# psx-mc.net
KiCad netlist of a schematic drawn in EAGLE
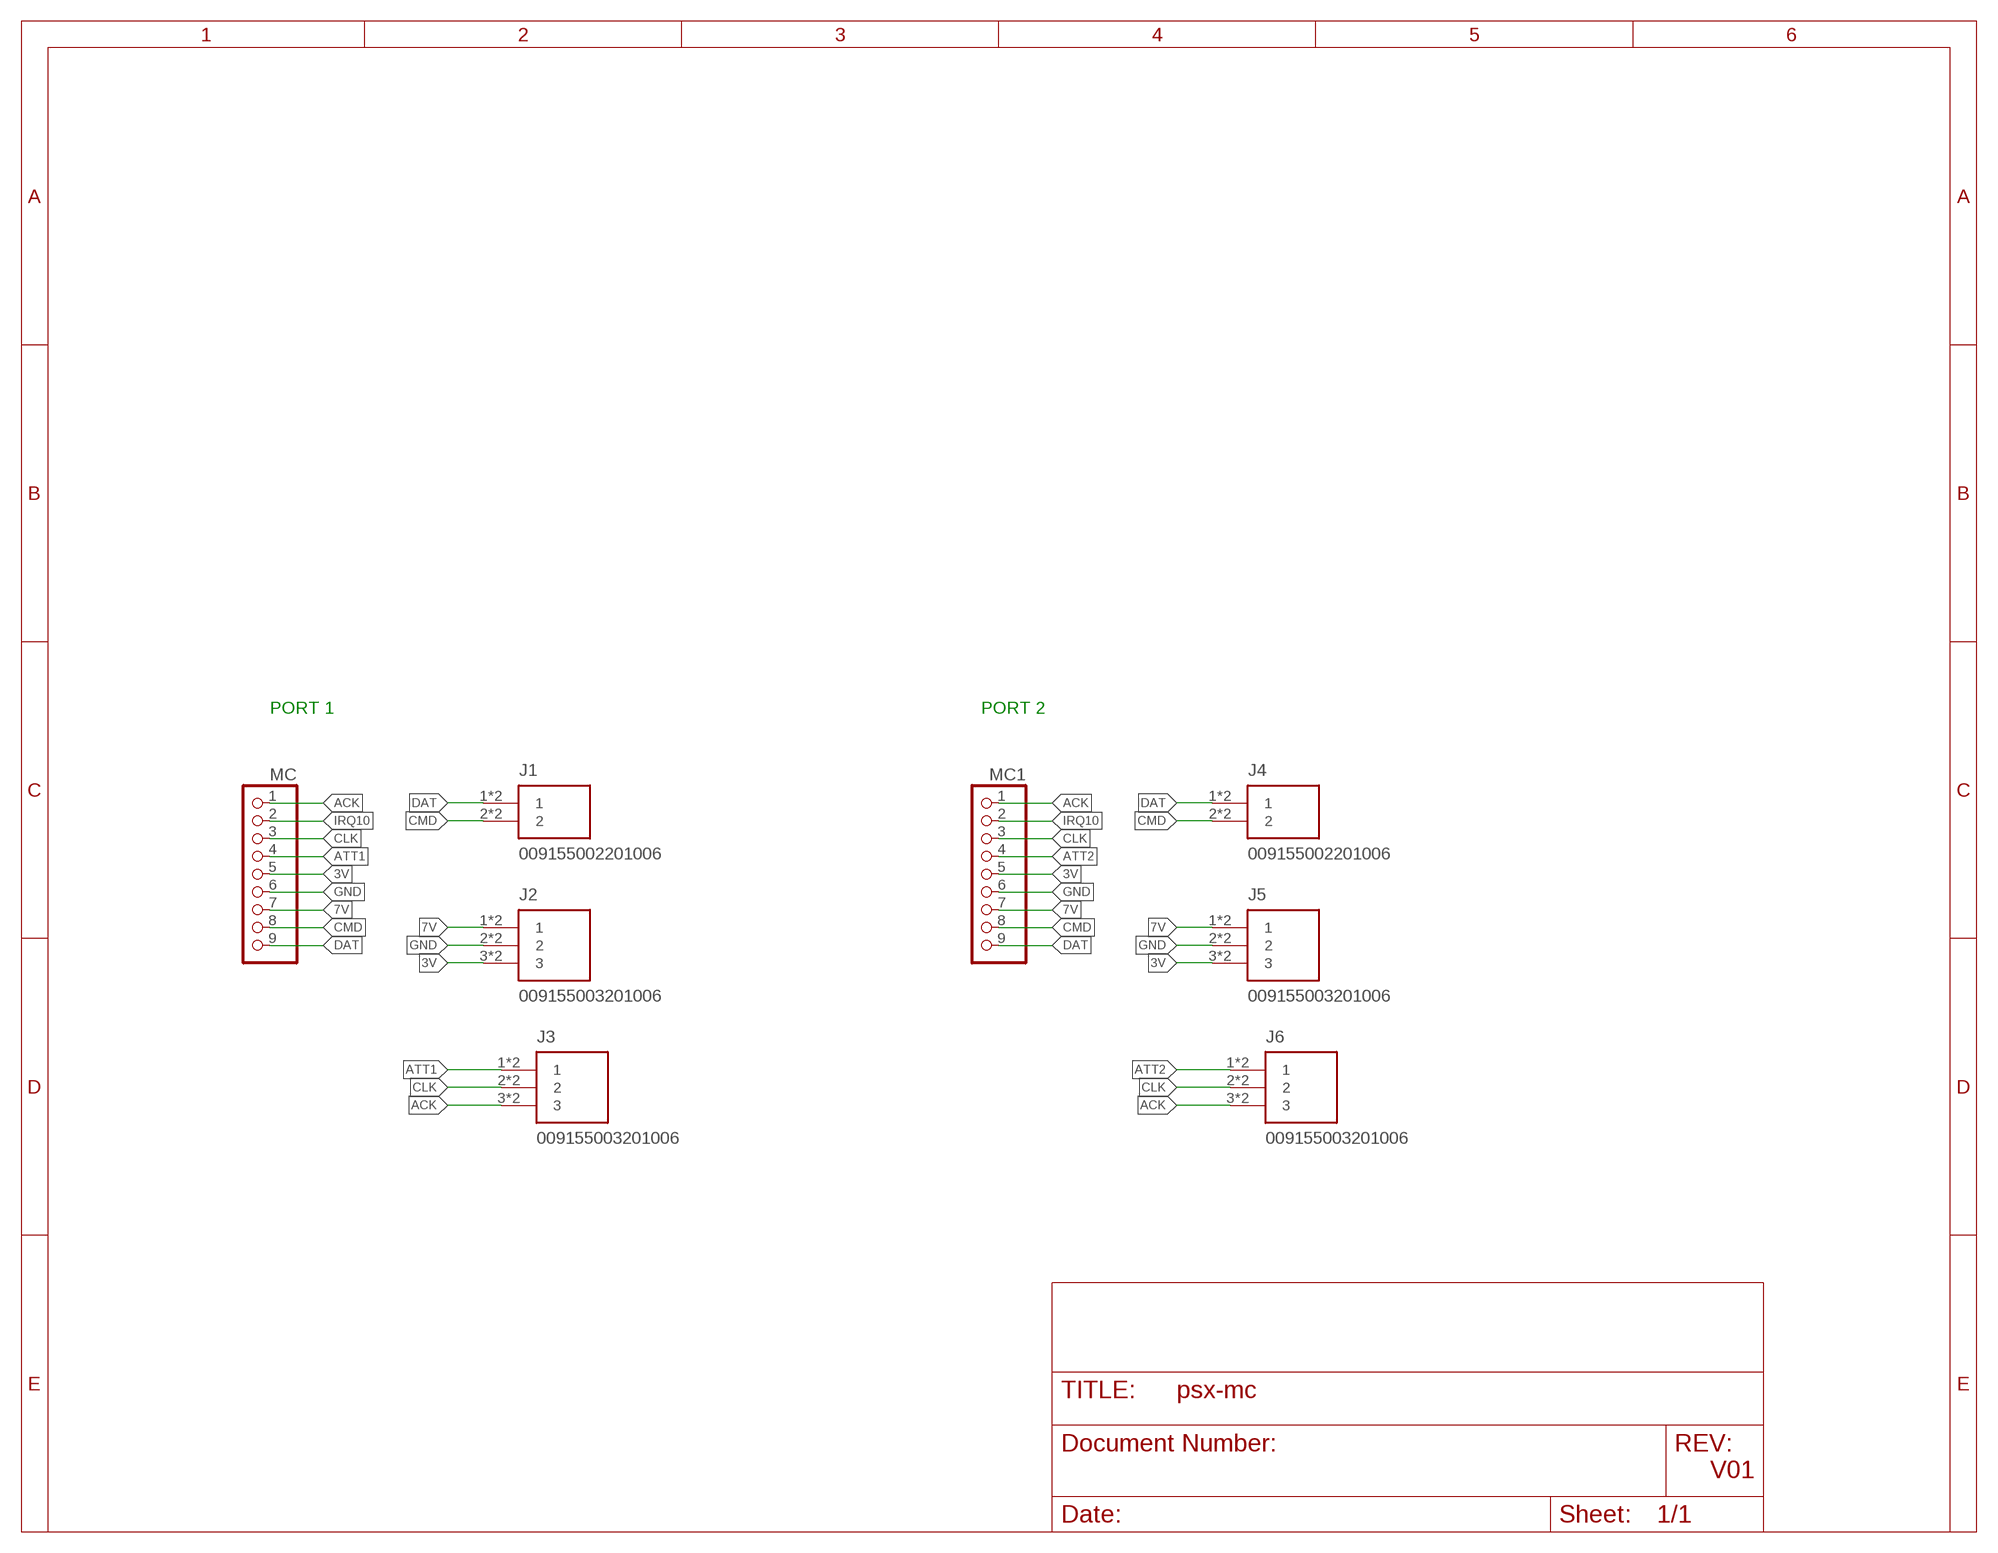
[diagram p0: schematic, sheet 1]

(export (version "E")
  (design (tool "Eeschema 10.0.6"))
  (components
    (comp (ref "J1")
      (value "009155002201006")
      (footprint "eagle-import:AVX_009155002201006")
      (fields (field (name "MF") "AVX"))
      (libsource (lib "eagle-import") (part "009155002201006"))
    )
    (comp (ref "J2")
      (value "009155003201006")
      (footprint "eagle-import:AVX_009155003201006")
      (fields (field (name "MF") "AVX"))
      (libsource (lib "eagle-import") (part "009155003201006"))
    )
    (comp (ref "J3")
      (value "009155003201006")
      (footprint "eagle-import:AVX_009155003201006")
      (fields (field (name "MF") "AVX"))
      (libsource (lib "eagle-import") (part "009155003201006"))
    )
    (comp (ref "J4")
      (value "009155002201006")
      (footprint "eagle-import:AVX_009155002201006")
      (fields (field (name "MF") "AVX"))
      (libsource (lib "eagle-import") (part "009155002201006"))
    )
    (comp (ref "J5")
      (value "009155003201006")
      (footprint "eagle-import:AVX_009155003201006")
      (fields (field (name "MF") "AVX"))
      (libsource (lib "eagle-import") (part "009155003201006"))
    )
    (comp (ref "J6")
      (value "009155003201006")
      (footprint "eagle-import:AVX_009155003201006")
      (fields (field (name "MF") "AVX"))
      (libsource (lib "eagle-import") (part "009155003201006"))
    )
    (comp (ref "MC")
      (value "PINHD-1X09_2.54-S")
      (footprint "eagle-import:1X09-S")
      (libsource (lib "eagle-import") (part "PINHD-1X09_2.54-S"))
    )
    (comp (ref "MC1")
      (value "PINHD-1X09_2.54-S")
      (footprint "eagle-import:1X09-S")
      (libsource (lib "eagle-import") (part "PINHD-1X09_2.54-S"))
    )
  )
  (nets
    (net (code "1") (name "3V") (class "Default")
      (node (ref "J2") (pin "3") (pinfunction "3_3") (pintype "passive"))
      (node (ref "J2") (pin "3_1") (pinfunction "3_3_1") (pintype "passive"))
      (node (ref "J5") (pin "3") (pinfunction "3_3") (pintype "passive"))
      (node (ref "J5") (pin "3_1") (pinfunction "3_3_1") (pintype "passive"))
      (node (ref "MC") (pin "5") (pinfunction "5_5") (pintype "passive"))
      (node (ref "MC1") (pin "5") (pinfunction "5_5") (pintype "passive"))
    )
    (net (code "2") (name "7V") (class "Default")
      (node (ref "J2") (pin "1") (pinfunction "1_1") (pintype "passive"))
      (node (ref "J2") (pin "1_1") (pinfunction "1_1_1") (pintype "passive"))
      (node (ref "J5") (pin "1") (pinfunction "1_1") (pintype "passive"))
      (node (ref "J5") (pin "1_1") (pinfunction "1_1_1") (pintype "passive"))
      (node (ref "MC") (pin "7") (pinfunction "7_7") (pintype "passive"))
      (node (ref "MC1") (pin "7") (pinfunction "7_7") (pintype "passive"))
    )
    (net (code "3") (name "ACK") (class "Default")
      (node (ref "J3") (pin "3") (pinfunction "3_3") (pintype "passive"))
      (node (ref "J3") (pin "3_1") (pinfunction "3_3_1") (pintype "passive"))
      (node (ref "J6") (pin "3") (pinfunction "3_3") (pintype "passive"))
      (node (ref "J6") (pin "3_1") (pinfunction "3_3_1") (pintype "passive"))
      (node (ref "MC") (pin "1") (pinfunction "1_1") (pintype "passive"))
      (node (ref "MC1") (pin "1") (pinfunction "1_1") (pintype "passive"))
    )
    (net (code "4") (name "ATT1") (class "Default")
      (node (ref "J3") (pin "1") (pinfunction "1_1") (pintype "passive"))
      (node (ref "J3") (pin "1_1") (pinfunction "1_1_1") (pintype "passive"))
      (node (ref "MC") (pin "4") (pinfunction "4_4") (pintype "passive"))
    )
    (net (code "5") (name "ATT2") (class "Default")
      (node (ref "J6") (pin "1") (pinfunction "1_1") (pintype "passive"))
      (node (ref "J6") (pin "1_1") (pinfunction "1_1_1") (pintype "passive"))
      (node (ref "MC1") (pin "4") (pinfunction "4_4") (pintype "passive"))
    )
    (net (code "6") (name "CLK") (class "Default")
      (node (ref "J3") (pin "2") (pinfunction "2_2") (pintype "passive"))
      (node (ref "J3") (pin "2_1") (pinfunction "2_2_1") (pintype "passive"))
      (node (ref "J6") (pin "2") (pinfunction "2_2") (pintype "passive"))
      (node (ref "J6") (pin "2_1") (pinfunction "2_2_1") (pintype "passive"))
      (node (ref "MC") (pin "3") (pinfunction "3_3") (pintype "passive"))
      (node (ref "MC1") (pin "3") (pinfunction "3_3") (pintype "passive"))
    )
    (net (code "7") (name "CMD") (class "Default")
      (node (ref "J1") (pin "2") (pinfunction "2_2") (pintype "passive"))
      (node (ref "J1") (pin "2_1") (pinfunction "2_2_1") (pintype "passive"))
      (node (ref "J4") (pin "2") (pinfunction "2_2") (pintype "passive"))
      (node (ref "J4") (pin "2_1") (pinfunction "2_2_1") (pintype "passive"))
      (node (ref "MC") (pin "8") (pinfunction "8_8") (pintype "passive"))
      (node (ref "MC1") (pin "8") (pinfunction "8_8") (pintype "passive"))
    )
    (net (code "8") (name "DAT") (class "Default")
      (node (ref "J1") (pin "1") (pinfunction "1_1") (pintype "passive"))
      (node (ref "J1") (pin "1_1") (pinfunction "1_1_1") (pintype "passive"))
      (node (ref "J4") (pin "1") (pinfunction "1_1") (pintype "passive"))
      (node (ref "J4") (pin "1_1") (pinfunction "1_1_1") (pintype "passive"))
      (node (ref "MC") (pin "9") (pinfunction "9_9") (pintype "passive"))
      (node (ref "MC1") (pin "9") (pinfunction "9_9") (pintype "passive"))
    )
    (net (code "9") (name "GND") (class "Default")
      (node (ref "J2") (pin "2") (pinfunction "2_2") (pintype "passive"))
      (node (ref "J2") (pin "2_1") (pinfunction "2_2_1") (pintype "passive"))
      (node (ref "J5") (pin "2") (pinfunction "2_2") (pintype "passive"))
      (node (ref "J5") (pin "2_1") (pinfunction "2_2_1") (pintype "passive"))
      (node (ref "MC") (pin "6") (pinfunction "6_6") (pintype "passive"))
      (node (ref "MC1") (pin "6") (pinfunction "6_6") (pintype "passive"))
    )
    (net (code "10") (name "IRQ10") (class "Default")
      (node (ref "MC") (pin "2") (pinfunction "2_2") (pintype "passive"))
      (node (ref "MC1") (pin "2") (pinfunction "2_2") (pintype "passive"))
    )
  )
)
